# ESP12_TEMP.net
KiCad netlist of a schematic drawn in EAGLE
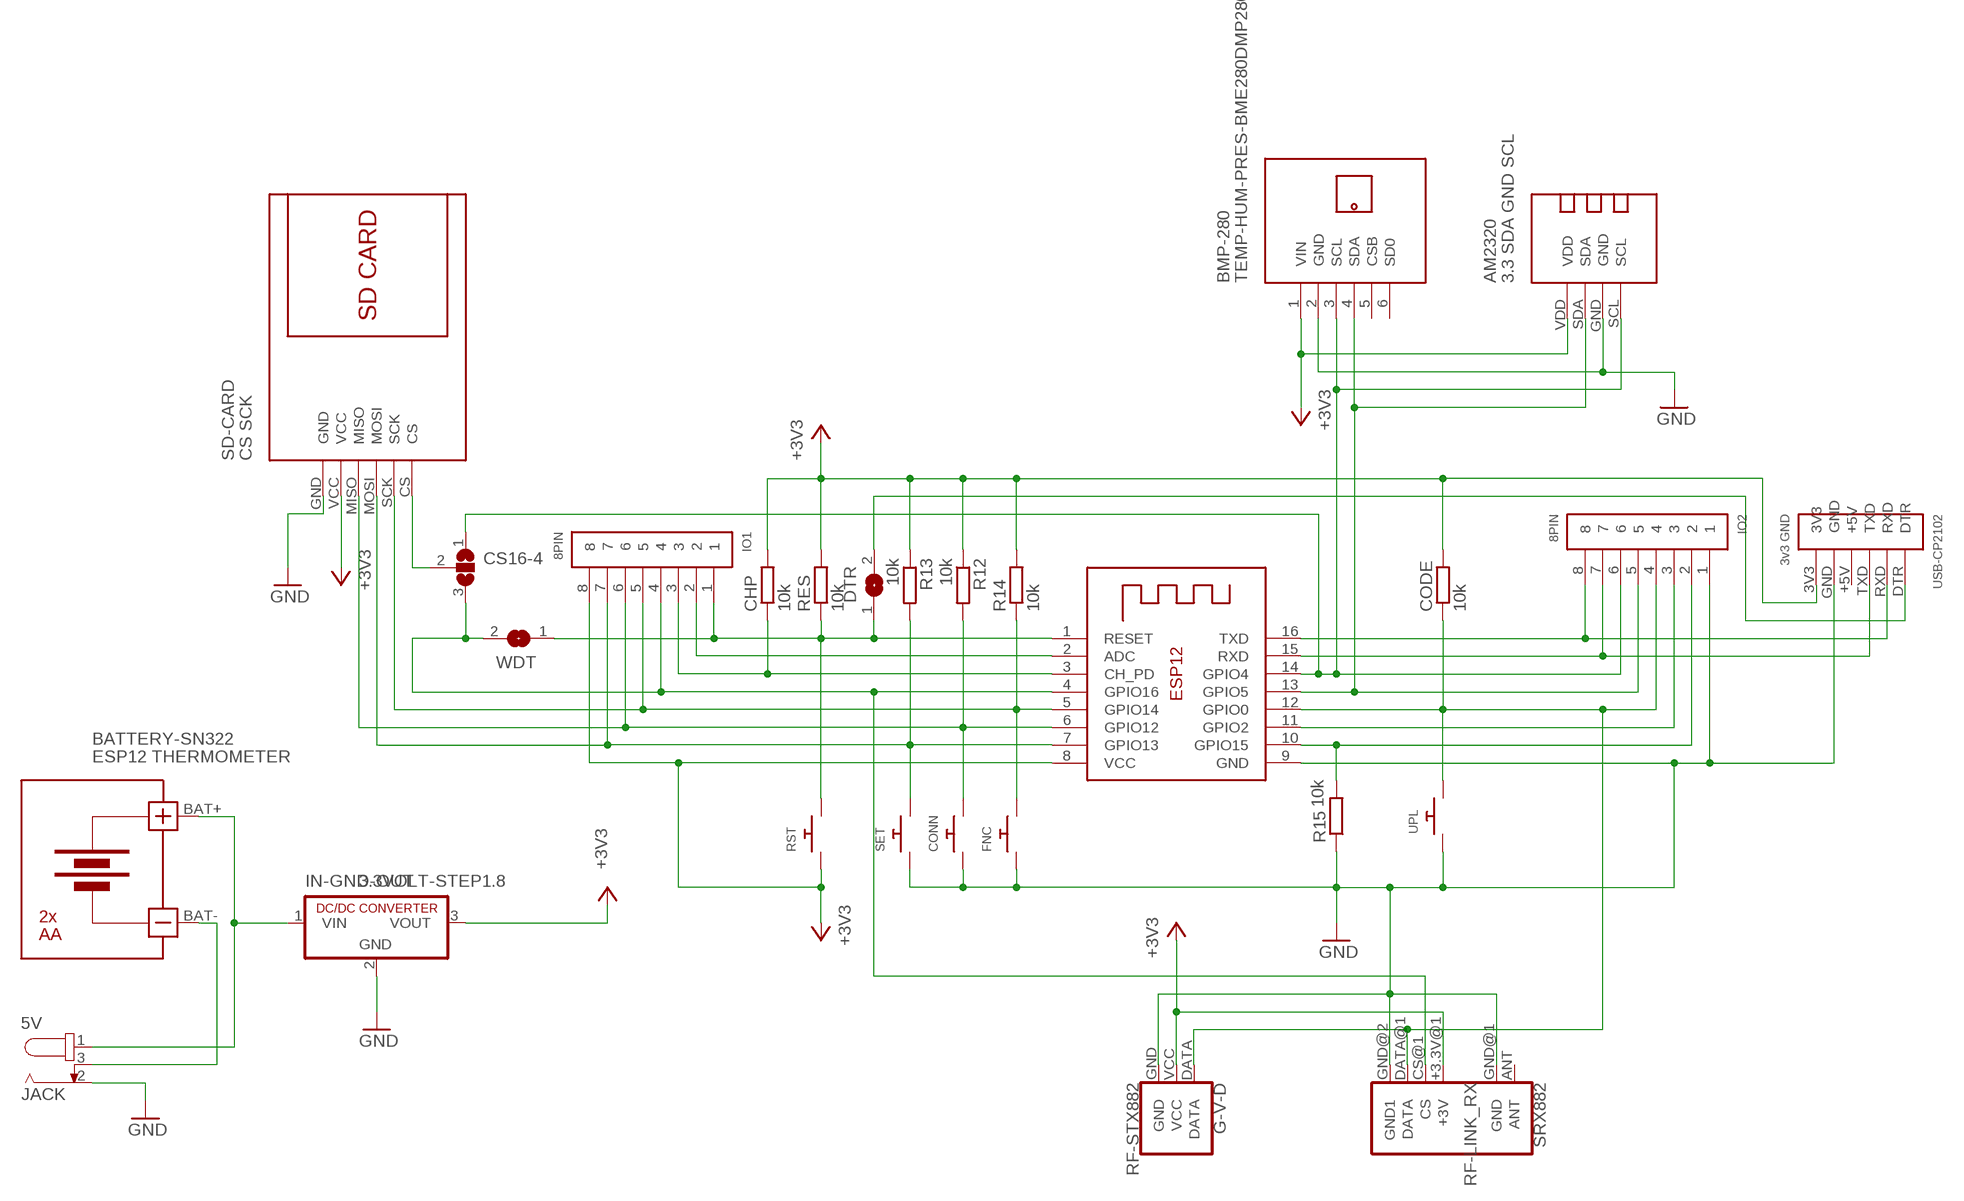
[diagram p0: schematic, sheet 1]

(export (version "E")
  (design (tool "Eeschema 10.0.6"))
  (components
    (comp (ref "5V")
      (value "JACK")
      (footprint "eagle-import:JACK")
      (fields
        (field (name "DIGIKEY_PART_NUMBER") "732-5925-ND")
        (field (name "MANUFACTURER") "Wurth Electronics Inc.")
        (field (name "MPN") "694103303002")
        (field (name "CREATED_BY") "PCBLayout.com")
      )
      (libsource (lib "eagle-import") (part "JACK"))
    )
    (comp (ref "AM2320")
      (value "3.3 SDA GND SCL")
      (footprint "eagle-import:TEMP-HUM-SENSOR-AM2322S")
      (libsource (lib "eagle-import") (part "TEMP-HUM-SENSOR-AM2320AM2320S"))
    )
    (comp (ref "BATTERY-SN322")
      (value "ESP12 THERMOMETER")
      (footprint "eagle-import:BATTERY-HOLDER-2AA")
      (libsource (lib "eagle-import") (part "BATTERY-HOLDER-2AA"))
    )
    (comp (ref "BMP-280")
      (value "TEMP-HUM-PRES-BME280DMP280S")
      (footprint "eagle-import:TEMP-HUM-PRES-BME280S")
      (libsource (lib "eagle-import") (part "TEMP-HUM-PRES-BME280DMP280S"))
    )
    (comp (ref "CHP")
      (value "10k")
      (footprint "eagle-import:0204_5")
      (libsource (lib "eagle-import") (part "R-5MM0204/5"))
    )
    (comp (ref "CODE")
      (value "10k")
      (footprint "eagle-import:0204_5")
      (libsource (lib "eagle-import") (part "R-5MM0204/5"))
    )
    (comp (ref "CONN")
      (value "SWITCH_PUSHBUTTONEVQ-PE")
      (footprint "eagle-import:TACT_PANA-EVQ")
      (libsource (lib "eagle-import") (part "SWITCH_PUSHBUTTONEVQ-PE"))
    )
    (comp (ref "CS16-4")
      (value "JUMERS3-SMD")
      (footprint "eagle-import:SJ_2")
      (libsource (lib "eagle-import") (part "JUMERS3-SMD"))
    )
    (comp (ref "DTR")
      (value "JUMPER-SMD")
      (footprint "eagle-import:SJ")
      (libsource (lib "eagle-import") (part "JUMPER-SMD"))
    )
    (comp (ref "ESP12E")
      (value "ESP-12")
      (footprint "eagle-import:ESP-12")
      (libsource (lib "eagle-import") (part "ESP-12"))
    )
    (comp (ref "FNC")
      (value "SWITCH_PUSHBUTTONEVQ-PE")
      (footprint "eagle-import:TACT_PANA-EVQ")
      (libsource (lib "eagle-import") (part "SWITCH_PUSHBUTTONEVQ-PE"))
    )
    (comp (ref "G-V-D")
      (value "RF-STX882")
      (footprint "eagle-import:RF-LINK_TX")
      (libsource (lib "eagle-import") (part "RF-LINK_TX"))
    )
    (comp (ref "IN-GND-OUT")
      (value "3.3VOLT-STEP1.8")
      (footprint "eagle-import:SIP3")
      (libsource (lib "eagle-import") (part "3.3VOLT-STEP1.8"))
    )
    (comp (ref "IO1")
      (value "8PIN")
      (footprint "eagle-import:8PIN")
      (fields
        (field (name "DIGI_KEY_PART_NUMBER") "732-5321-ND")
        (field (name "MANUFACTURER") "Wurth Electronics Inc.")
        (field (name "MPN") "61300811121")
        (field (name "CREATED_BY") "PCBLayout.com")
      )
      (libsource (lib "eagle-import") (part "8PIN"))
    )
    (comp (ref "IO2")
      (value "8PIN")
      (footprint "eagle-import:8PIN")
      (fields
        (field (name "DIGI_KEY_PART_NUMBER") "732-5321-ND")
        (field (name "MANUFACTURER") "Wurth Electronics Inc.")
        (field (name "MPN") "61300811121")
        (field (name "CREATED_BY") "PCBLayout.com")
      )
      (libsource (lib "eagle-import") (part "8PIN"))
    )
    (comp (ref "R12")
      (value "10k")
      (footprint "eagle-import:0204_5")
      (libsource (lib "eagle-import") (part "R-5MM0204/5"))
    )
    (comp (ref "R13")
      (value "10k")
      (footprint "eagle-import:0204_5")
      (libsource (lib "eagle-import") (part "R-5MM0204/5"))
    )
    (comp (ref "R14")
      (value "10k")
      (footprint "eagle-import:0204_5")
      (libsource (lib "eagle-import") (part "R-5MM0204/5"))
    )
    (comp (ref "R15")
      (value "10k")
      (footprint "eagle-import:0204_5")
      (libsource (lib "eagle-import") (part "R-5MM0204/5"))
    )
    (comp (ref "RES")
      (value "10k")
      (footprint "eagle-import:0204_5")
      (libsource (lib "eagle-import") (part "R-5MM0204/5"))
    )
    (comp (ref "RST")
      (value "SWITCH_PUSHBUTTONEVQ-PE")
      (footprint "eagle-import:TACT_PANA-EVQ")
      (libsource (lib "eagle-import") (part "SWITCH_PUSHBUTTONEVQ-PE"))
    )
    (comp (ref "SD-CARD")
      (value "CS SCK")
      (footprint "eagle-import:CARD-SD-ADAPTERS")
      (libsource (lib "eagle-import") (part "CARD-SD-ADAPTERSD-CARD"))
    )
    (comp (ref "SET")
      (value "SWITCH_PUSHBUTTONEVQ-PE")
      (footprint "eagle-import:TACT_PANA-EVQ")
      (libsource (lib "eagle-import") (part "SWITCH_PUSHBUTTONEVQ-PE"))
    )
    (comp (ref "SRX882")
      (value "RF-LINK_RX")
      (footprint "eagle-import:RF-LINK_RX")
      (libsource (lib "eagle-import") (part "RF-LINK_RX"))
    )
    (comp (ref "UPL")
      (value "SWITCH_PUSHBUTTONEVQ-PE")
      (footprint "eagle-import:TACT_PANA-EVQ")
      (libsource (lib "eagle-import") (part "SWITCH_PUSHBUTTONEVQ-PE"))
    )
    (comp (ref "USB-CP2102")
      (value "3v3 GND")
      (footprint "eagle-import:USB-UART")
      (fields
        (field (name "DIGI_KEY_PART_NUMBER") "732-5319-ND")
        (field (name "MANUFACTURER") "Wurth Electronics Inc.")
        (field (name "MPN") "61300611121")
        (field (name "CREATED_BY") "PCBLayout.com")
      )
      (libsource (lib "eagle-import") (part "USB-UART"))
    )
    (comp (ref "WDT")
      (value "JUMPER-SMD")
      (footprint "eagle-import:SJ")
      (libsource (lib "eagle-import") (part "JUMPER-SMD"))
    )
  )
  (nets
    (net (code "1") (name "+3V3") (class "Default")
      (node (ref "AM2320") (pin "VDD") (pinfunction "VDD_VDD") (pintype "power_in"))
      (node (ref "BMP-280") (pin "1") (pinfunction "VIN_1") (pintype "power_in"))
      (node (ref "CHP") (pin "2") (pinfunction "2_2") (pintype "passive"))
      (node (ref "CODE") (pin "2") (pinfunction "2_2") (pintype "passive"))
      (node (ref "ESP12E") (pin "8") (pinfunction "VCC_8") (pintype "power_in"))
      (node (ref "G-V-D") (pin "VCC") (pinfunction "VCC_VCC") (pintype "power_in"))
      (node (ref "IN-GND-OUT") (pin "3") (pinfunction "VOUT_3") (pintype "passive"))
      (node (ref "IO1") (pin "8") (pinfunction "8_8") (pintype "passive"))
      (node (ref "R12") (pin "1") (pinfunction "1_1") (pintype "passive"))
      (node (ref "R13") (pin "1") (pinfunction "1_1") (pintype "passive"))
      (node (ref "R14") (pin "2") (pinfunction "2_2") (pintype "passive"))
      (node (ref "RES") (pin "2") (pinfunction "2_2") (pintype "passive"))
      (node (ref "RST") (pin "P$1") (pinfunction "P$1_P$1") (pintype "passive"))
      (node (ref "SD-CARD") (pin "VCC") (pinfunction "VCC_VCC") (pintype "power_in"))
      (node (ref "SRX882") (pin "+3.3V@1") (pinfunction "+3V_+3.3V@1") (pintype "power_in"))
      (node (ref "USB-CP2102") (pin "3V3") (pinfunction "3V3_3V3") (pintype "power_in"))
    )
    (net (code "2") (name "/+5V") (class "Default")
      (node (ref "USB-CP2102") (pin "+5V") (pinfunction "+5V_+5V") (pintype "power_in"))
    )
    (net (code "3") (name "GND") (class "Default")
      (node (ref "5V") (pin "2") (pinfunction "2_2") (pintype "passive"))
      (node (ref "AM2320") (pin "GND") (pinfunction "GND_GND") (pintype "power_in"))
      (node (ref "BMP-280") (pin "2") (pinfunction "GND_2") (pintype "power_in"))
      (node (ref "CONN") (pin "P$1") (pinfunction "P$1_P$1") (pintype "passive"))
      (node (ref "ESP12E") (pin "9") (pinfunction "GND_9") (pintype "power_in"))
      (node (ref "FNC") (pin "P$1") (pinfunction "P$1_P$1") (pintype "passive"))
      (node (ref "G-V-D") (pin "GND") (pinfunction "GND_GND") (pintype "power_in"))
      (node (ref "IN-GND-OUT") (pin "2") (pinfunction "GND_2") (pintype "passive"))
      (node (ref "IO2") (pin "1") (pinfunction "1_1") (pintype "passive"))
      (node (ref "R15") (pin "1") (pinfunction "1_1") (pintype "passive"))
      (node (ref "SD-CARD") (pin "GND") (pinfunction "GND_GND") (pintype "power_in"))
      (node (ref "SET") (pin "P$1") (pinfunction "P$1_P$1") (pintype "passive"))
      (node (ref "SRX882") (pin "GND@1") (pinfunction "GND_GND@1") (pintype "power_in"))
      (node (ref "SRX882") (pin "GND@2") (pinfunction "GND1_GND@2") (pintype "power_in"))
      (node (ref "UPL") (pin "P$1") (pinfunction "P$1_P$1") (pintype "passive"))
      (node (ref "USB-CP2102") (pin "GND") (pinfunction "GND_GND") (pintype "power_in"))
    )
    (net (code "4") (name "Net-(5V-Pad3)") (class "Default")
      (node (ref "5V") (pin "3") (pinfunction "3_3") (pintype "passive"))
      (node (ref "BATTERY-SN322") (pin "BAT-") (pinfunction "BAT-_BAT-") (pintype "power_in"))
    )
    (net (code "5") (name "Net-(BMP-280-SCL)") (class "Default")
      (node (ref "AM2320") (pin "SCL") (pinfunction "SCL_SCL") (pintype "bidirectional"))
      (node (ref "BMP-280") (pin "3") (pinfunction "SCL_3") (pintype "bidirectional"))
      (node (ref "CS16-4") (pin "1") (pinfunction "1_1") (pintype "passive"))
      (node (ref "ESP12E") (pin "14") (pinfunction "GPIO4_14") (pintype "bidirectional"))
      (node (ref "IO2") (pin "6") (pinfunction "6_6") (pintype "passive"))
    )
    (net (code "6") (name "Net-(BMP-280-SDA)") (class "Default")
      (node (ref "AM2320") (pin "SDA") (pinfunction "SDA_SDA") (pintype "bidirectional"))
      (node (ref "BMP-280") (pin "4") (pinfunction "SDA_4") (pintype "bidirectional"))
      (node (ref "ESP12E") (pin "13") (pinfunction "GPIO5_13") (pintype "bidirectional"))
      (node (ref "IO2") (pin "5") (pinfunction "5_5") (pintype "passive"))
    )
    (net (code "7") (name "Net-(CS16-4-Pad2)") (class "Default")
      (node (ref "CS16-4") (pin "2") (pinfunction "2_2") (pintype "passive"))
      (node (ref "SD-CARD") (pin "CS") (pinfunction "CS_CS") (pintype "bidirectional"))
    )
    (net (code "8") (name "Net-(DTR-Pad2)") (class "Default")
      (node (ref "DTR") (pin "2") (pinfunction "2_2") (pintype "passive"))
      (node (ref "USB-CP2102") (pin "DTR") (pinfunction "DTR_DTR") (pintype "bidirectional"))
    )
    (net (code "9") (name "Net-(ESP12E-ADC)") (class "Default")
      (node (ref "ESP12E") (pin "2") (pinfunction "ADC_2") (pintype "passive"))
      (node (ref "IO1") (pin "2") (pinfunction "2_2") (pintype "passive"))
    )
    (net (code "10") (name "Net-(ESP12E-CH_PD)") (class "Default")
      (node (ref "CHP") (pin "1") (pinfunction "1_1") (pintype "passive"))
      (node (ref "ESP12E") (pin "3") (pinfunction "CH_PD_3") (pintype "input"))
      (node (ref "IO1") (pin "3") (pinfunction "3_3") (pintype "passive"))
    )
    (net (code "11") (name "Net-(ESP12E-GPIO0)") (class "Default")
      (node (ref "CODE") (pin "1") (pinfunction "1_1") (pintype "passive"))
      (node (ref "ESP12E") (pin "12") (pinfunction "GPIO0_12") (pintype "bidirectional"))
      (node (ref "G-V-D") (pin "DATA") (pinfunction "DATA_DATA") (pintype "bidirectional"))
      (node (ref "IO2") (pin "4") (pinfunction "4_4") (pintype "passive"))
      (node (ref "SRX882") (pin "DATA@1") (pinfunction "DATA_DATA@1") (pintype "input"))
      (node (ref "UPL") (pin "P$2") (pinfunction "P$2_P$2") (pintype "passive"))
    )
    (net (code "12") (name "Net-(ESP12E-GPIO2)") (class "Default")
      (node (ref "ESP12E") (pin "11") (pinfunction "GPIO2_11") (pintype "bidirectional"))
      (node (ref "IO2") (pin "3") (pinfunction "3_3") (pintype "passive"))
    )
    (net (code "13") (name "Net-(ESP12E-GPIO12)") (class "Default")
      (node (ref "CONN") (pin "P$2") (pinfunction "P$2_P$2") (pintype "passive"))
      (node (ref "ESP12E") (pin "6") (pinfunction "GPIO12_6") (pintype "bidirectional"))
      (node (ref "IO1") (pin "6") (pinfunction "6_6") (pintype "passive"))
      (node (ref "R12") (pin "2") (pinfunction "2_2") (pintype "passive"))
      (node (ref "SD-CARD") (pin "MISO") (pinfunction "MISO_MISO") (pintype "bidirectional"))
    )
    (net (code "14") (name "Net-(ESP12E-GPIO13)") (class "Default")
      (node (ref "ESP12E") (pin "7") (pinfunction "GPIO13_7") (pintype "bidirectional"))
      (node (ref "IO1") (pin "7") (pinfunction "7_7") (pintype "passive"))
      (node (ref "R13") (pin "2") (pinfunction "2_2") (pintype "passive"))
      (node (ref "SD-CARD") (pin "MOSI") (pinfunction "MOSI_MOSI") (pintype "bidirectional"))
      (node (ref "SET") (pin "P$2") (pinfunction "P$2_P$2") (pintype "passive"))
    )
    (net (code "15") (name "Net-(ESP12E-GPIO14)") (class "Default")
      (node (ref "ESP12E") (pin "5") (pinfunction "GPIO14_5") (pintype "bidirectional"))
      (node (ref "FNC") (pin "P$2") (pinfunction "P$2_P$2") (pintype "passive"))
      (node (ref "IO1") (pin "5") (pinfunction "5_5") (pintype "passive"))
      (node (ref "R14") (pin "1") (pinfunction "1_1") (pintype "passive"))
      (node (ref "SD-CARD") (pin "SCK") (pinfunction "SCK_SCK") (pintype "bidirectional"))
    )
    (net (code "16") (name "Net-(ESP12E-GPIO15)") (class "Default")
      (node (ref "ESP12E") (pin "10") (pinfunction "GPIO15_10") (pintype "bidirectional"))
      (node (ref "IO2") (pin "2") (pinfunction "2_2") (pintype "passive"))
      (node (ref "R15") (pin "2") (pinfunction "2_2") (pintype "passive"))
    )
    (net (code "17") (name "Net-(ESP12E-GPIO16)") (class "Default")
      (node (ref "CS16-4") (pin "3") (pinfunction "3_3") (pintype "passive"))
      (node (ref "ESP12E") (pin "4") (pinfunction "GPIO16_4") (pintype "bidirectional"))
      (node (ref "IO1") (pin "4") (pinfunction "4_4") (pintype "passive"))
      (node (ref "SRX882") (pin "CS@1") (pinfunction "CS_CS@1") (pintype "bidirectional"))
      (node (ref "WDT") (pin "2") (pinfunction "2_2") (pintype "passive"))
    )
    (net (code "18") (name "Net-(ESP12E-RESET)") (class "Default")
      (node (ref "DTR") (pin "1") (pinfunction "1_1") (pintype "passive"))
      (node (ref "ESP12E") (pin "1") (pinfunction "RESET_1") (pintype "input"))
      (node (ref "IO1") (pin "1") (pinfunction "1_1") (pintype "passive"))
      (node (ref "RES") (pin "1") (pinfunction "1_1") (pintype "passive"))
      (node (ref "RST") (pin "P$2") (pinfunction "P$2_P$2") (pintype "passive"))
      (node (ref "WDT") (pin "1") (pinfunction "1_1") (pintype "passive"))
    )
    (net (code "19") (name "Net-(ESP12E-RXD)") (class "Default")
      (node (ref "ESP12E") (pin "15") (pinfunction "RXD_15") (pintype "input"))
      (node (ref "IO2") (pin "7") (pinfunction "7_7") (pintype "passive"))
      (node (ref "USB-CP2102") (pin "TXD") (pinfunction "TXD_TXD") (pintype "output"))
    )
    (net (code "20") (name "Net-(ESP12E-TXD)") (class "Default")
      (node (ref "ESP12E") (pin "16") (pinfunction "TXD_16") (pintype "output"))
      (node (ref "IO2") (pin "8") (pinfunction "8_8") (pintype "passive"))
      (node (ref "USB-CP2102") (pin "RXD") (pinfunction "RXD_RXD") (pintype "input"))
    )
    (net (code "21") (name "Net-(IN-GND-OUT-VIN)") (class "Default")
      (node (ref "5V") (pin "1") (pinfunction "1_1") (pintype "passive"))
      (node (ref "BATTERY-SN322") (pin "BAT+") (pinfunction "BAT+_BAT+") (pintype "power_in"))
      (node (ref "IN-GND-OUT") (pin "1") (pinfunction "VIN_1") (pintype "passive"))
    )
    (net (code "22") (name "unconnected-(BMP-280-CSB-Pad5)") (class "Default")
      (node (ref "BMP-280") (pin "5") (pinfunction "CSB_5") (pintype "bidirectional"))
    )
    (net (code "23") (name "unconnected-(BMP-280-SD0-Pad6)") (class "Default")
      (node (ref "BMP-280") (pin "6") (pinfunction "SD0_6") (pintype "bidirectional"))
    )
    (net (code "24") (name "unconnected-(SRX882-PadANT)") (class "Default")
      (node (ref "SRX882") (pin "ANT") (pinfunction "ANT_ANT") (pintype "passive"))
    )
  )
)
